# ADS1293.net
KiCad netlist of a schematic drawn in EasyEDA
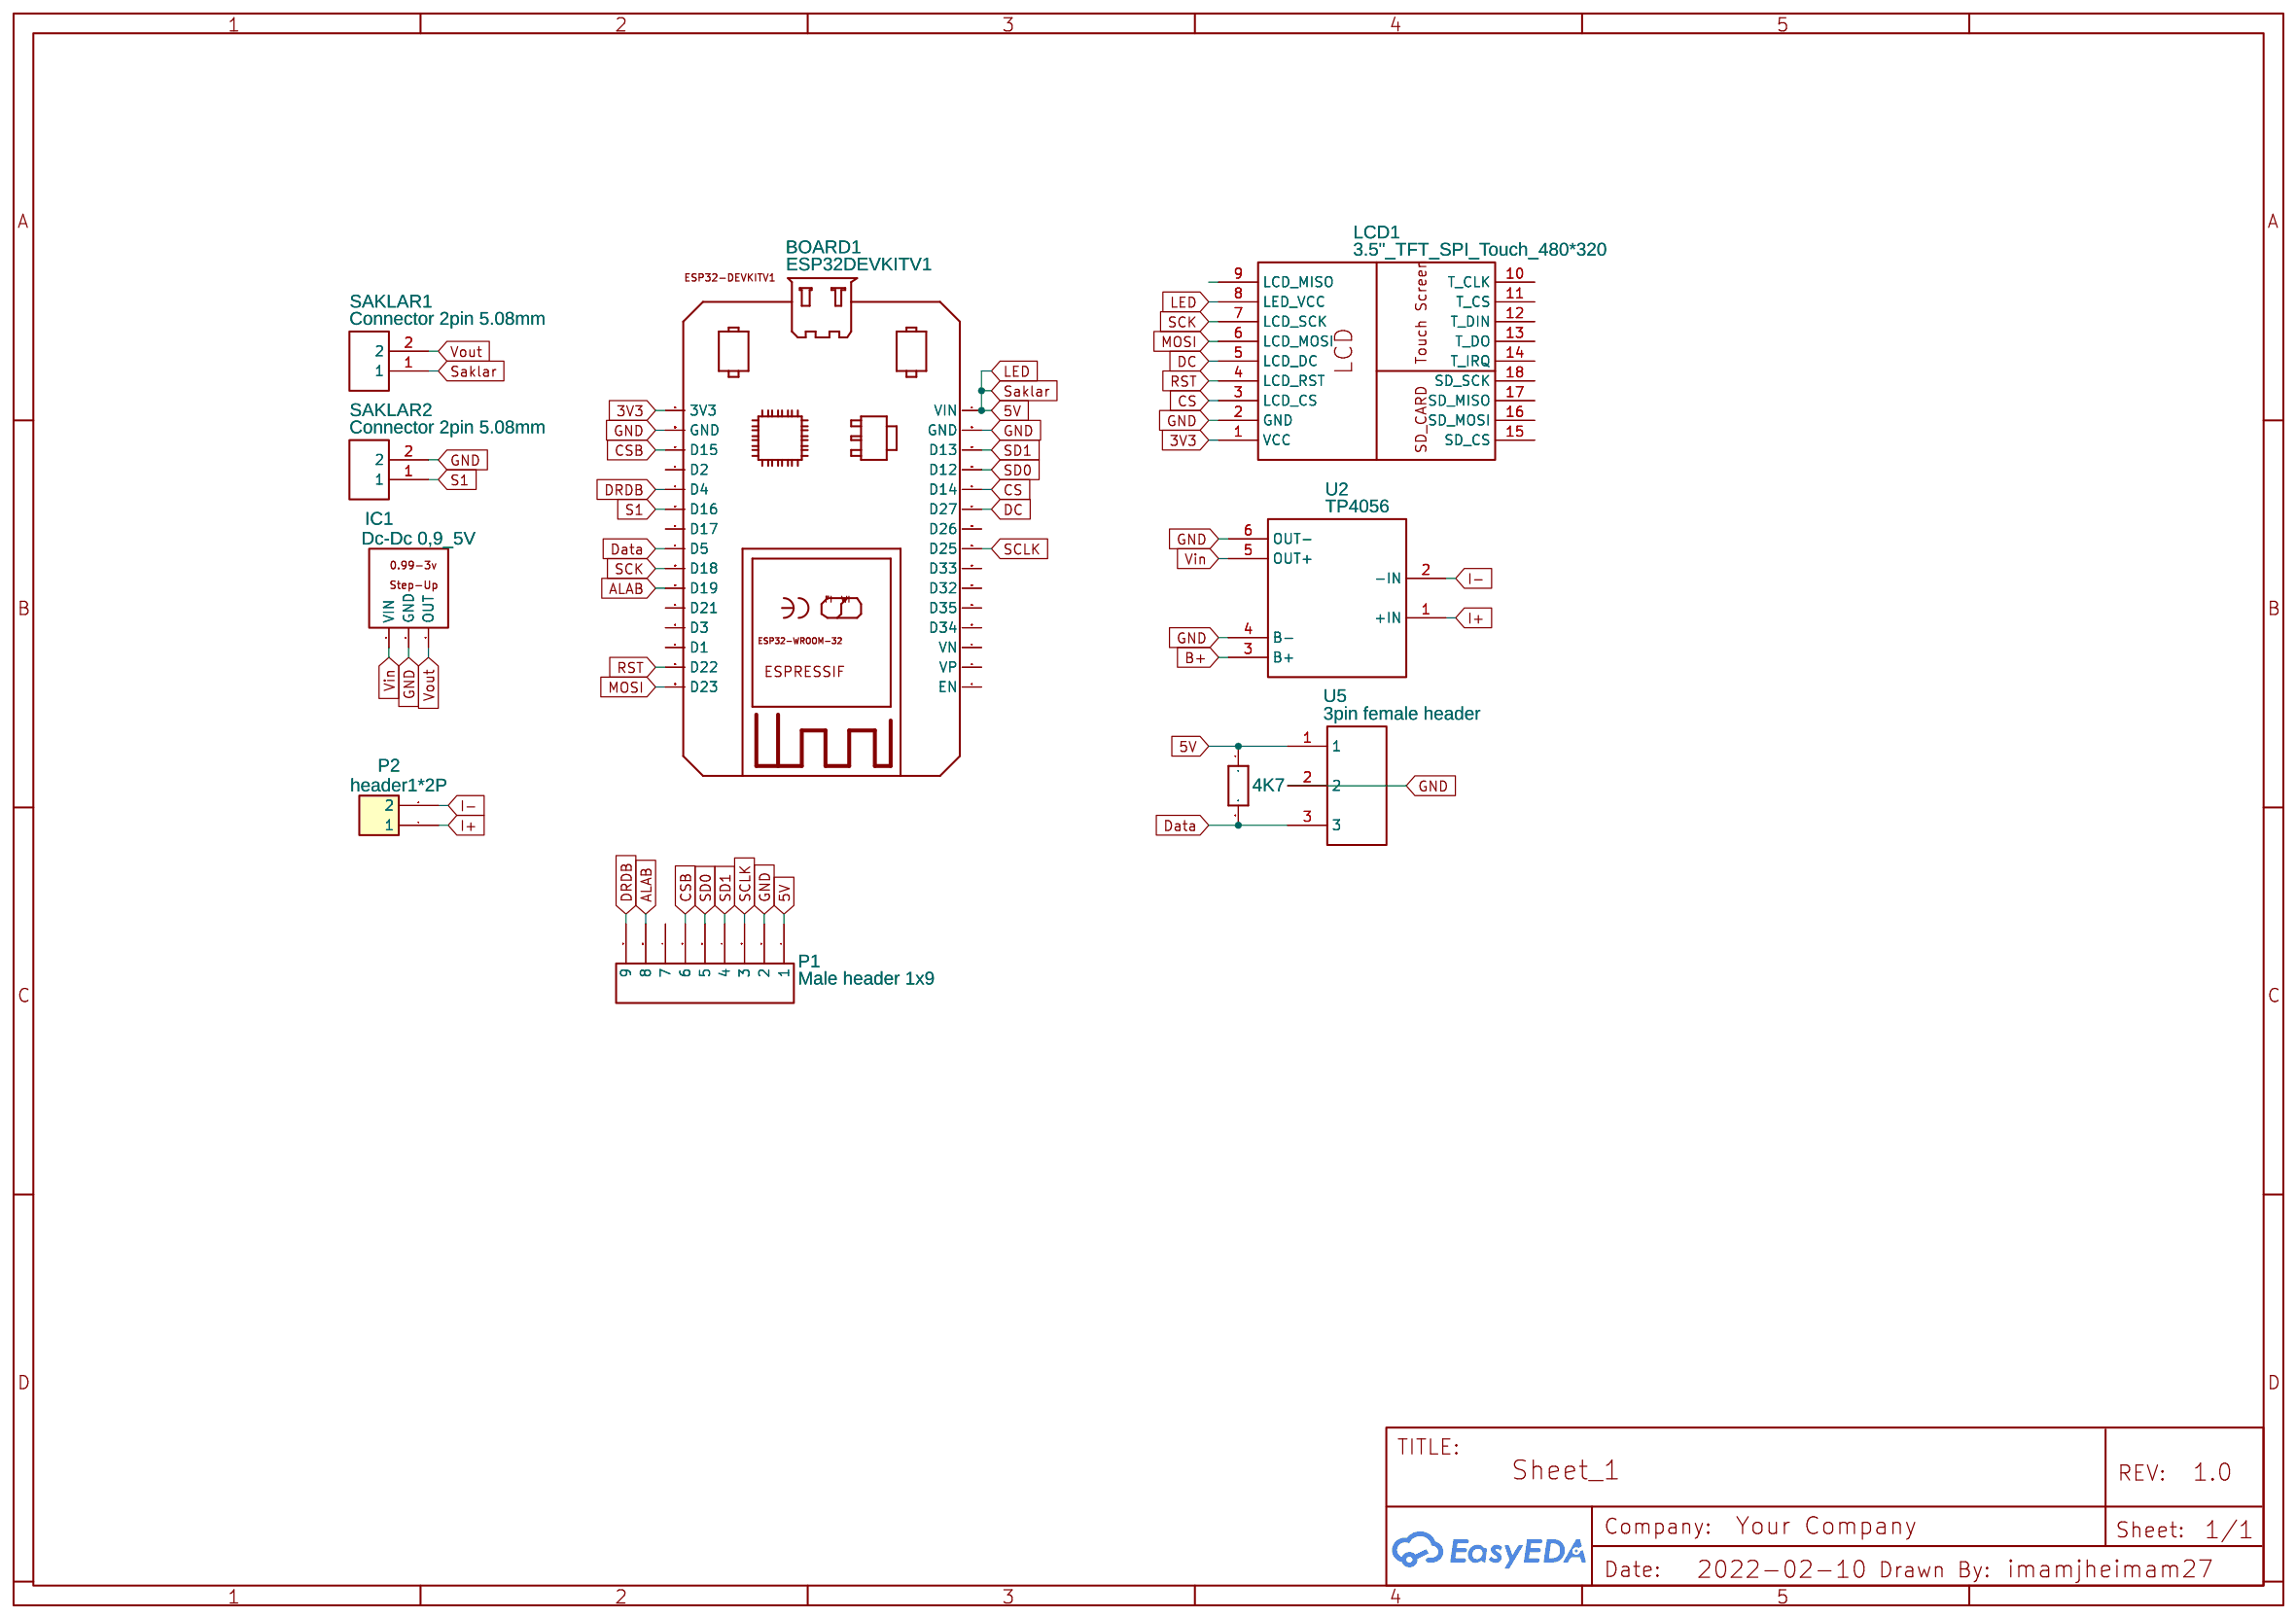
[diagram p0: schematic sheet]

(export (version "E")
  (design (tool "Eeschema 10.0.6"))
  (components
    (comp (ref "4K7") (value ".") (libsource (lib "") (part "NFR25H0002208J")))
    (comp (ref "BOARD1") (value "ESP32DEVKITV1") (libsource (lib "") (part "ESP32DEVKITV1")))
    (comp (ref "IC1") (value "Dc-Dc 0,9_5V") (libsource (lib "") (part "Dc-Dc 0,9_5V")))
    (comp (ref "LCD1")
      (value "3.5\"_TFT_SPI_Touch_480*320")
      (fields (field (name "BOM_Manufacturer Part") "ILI 9488"))
      (libsource (lib "") (part "3.5&quot;_TFT_SPI_Touch_480*320"))
    )
    (comp (ref "P1")
      (value "Male header 1x9")
      (fields
        (field (name "BOM_Manufacturer Part") "Pin Header 2.54mm Pitch 11 Pin Female Single Row Right Angle Strip")
      )
      (libsource (lib "") (part "Male header 1x9"))
    )
    (comp (ref "P2") (value "header1*2P") (libsource (lib "") (part "header1*2P")))
    (comp (ref "SAKLAR1") (value "Connector 2pin 5.08mm") (libsource (lib "") (part "Connector 2pin 5.08mm")))
    (comp (ref "SAKLAR2") (value "Connector 2pin 5.08mm") (libsource (lib "") (part "Connector 2pin 5.08mm")))
    (comp (ref "U2") (value "TP4056") (libsource (lib "") (part "TP4056")))
    (comp (ref "U5") (value "3pin female header") (libsource (lib "") (part "3pin female header")))
  )
  (nets
    (net (code "1") (name "3V3") (class "Default")
      (node (ref "BOARD1") (pin "3V3") (pinfunction "3V3_3V3") (pintype "bidirectional"))
      (node (ref "LCD1") (pin "1") (pinfunction "VCC_1") (pintype "unspecified"))
    )
    (net (code "2") (name "5V") (class "Default")
      (node (ref "4K7") (pin "1") (pinfunction "1_1") (pintype "bidirectional"))
      (node (ref "BOARD1") (pin "VIN") (pinfunction "VIN_VIN") (pintype "bidirectional"))
      (node (ref "LCD1") (pin "8") (pinfunction "LED_VCC_8") (pintype "unspecified"))
      (node (ref "P1") (pin "1") (pinfunction "1_1") (pintype "input"))
      (node (ref "SAKLAR1") (pin "1") (pinfunction "1_1") (pintype "unspecified"))
      (node (ref "U5") (pin "1") (pinfunction "1_1") (pintype "unspecified"))
    )
    (net (code "3") (name "ALAB") (class "Default")
      (node (ref "BOARD1") (pin "D19") (pinfunction "D19_D19") (pintype "bidirectional"))
      (node (ref "P1") (pin "8") (pinfunction "8_8") (pintype "input"))
    )
    (net (code "4") (name "B+") (class "Default")
      (node (ref "U2") (pin "3") (pinfunction "B+_3") (pintype "unspecified"))
    )
    (net (code "5") (name "CS") (class "Default")
      (node (ref "BOARD1") (pin "D14") (pinfunction "D14_D14") (pintype "bidirectional"))
      (node (ref "LCD1") (pin "3") (pinfunction "LCD_CS_3") (pintype "unspecified"))
    )
    (net (code "6") (name "CSB") (class "Default")
      (node (ref "BOARD1") (pin "D15") (pinfunction "D15_D15") (pintype "bidirectional"))
      (node (ref "P1") (pin "6") (pinfunction "6_6") (pintype "input"))
    )
    (net (code "7") (name "DC") (class "Default")
      (node (ref "BOARD1") (pin "D27") (pinfunction "D27_D27") (pintype "bidirectional"))
      (node (ref "LCD1") (pin "5") (pinfunction "LCD_DC_5") (pintype "unspecified"))
    )
    (net (code "8") (name "DRDB") (class "Default")
      (node (ref "BOARD1") (pin "D4") (pinfunction "D4_D4") (pintype "bidirectional"))
      (node (ref "P1") (pin "9") (pinfunction "9_9") (pintype "input"))
    )
    (net (code "9") (name "Data") (class "Default")
      (node (ref "4K7") (pin "2") (pinfunction "2_2") (pintype "bidirectional"))
      (node (ref "BOARD1") (pin "D5") (pinfunction "D5_D5") (pintype "bidirectional"))
      (node (ref "U5") (pin "3") (pinfunction "3_3") (pintype "unspecified"))
    )
    (net (code "10") (name "GND") (class "Default")
      (node (ref "BOARD1") (pin "GND") (pinfunction "GND_GND") (pintype "bidirectional"))
      (node (ref "BOARD1") (pin "GND@1") (pinfunction "GND_GND@1") (pintype "bidirectional"))
      (node (ref "IC1") (pin "2") (pinfunction "GND_2") (pintype "unspecified"))
      (node (ref "LCD1") (pin "2") (pinfunction "GND_2") (pintype "unspecified"))
      (node (ref "P1") (pin "2") (pinfunction "2_2") (pintype "input"))
      (node (ref "SAKLAR2") (pin "2") (pinfunction "2_2") (pintype "unspecified"))
      (node (ref "U2") (pin "4") (pinfunction "B-_4") (pintype "unspecified"))
      (node (ref "U2") (pin "6") (pinfunction "OUT-_6") (pintype "unspecified"))
      (node (ref "U5") (pin "2") (pinfunction "2_2") (pintype "unspecified"))
    )
    (net (code "11") (name "I+") (class "Default")
      (node (ref "P2") (pin "1") (pinfunction "1_1") (pintype "input"))
      (node (ref "U2") (pin "1") (pinfunction "+IN_1") (pintype "unspecified"))
    )
    (net (code "12") (name "I-") (class "Default")
      (node (ref "P2") (pin "2") (pinfunction "2_2") (pintype "input"))
      (node (ref "U2") (pin "2") (pinfunction "-IN_2") (pintype "unspecified"))
    )
    (net (code "13") (name "MOSI") (class "Default")
      (node (ref "BOARD1") (pin "D23") (pinfunction "D23_D23") (pintype "bidirectional"))
      (node (ref "LCD1") (pin "6") (pinfunction "LCD_MOSI_6") (pintype "unspecified"))
    )
    (net (code "14") (name "RST") (class "Default")
      (node (ref "BOARD1") (pin "D22") (pinfunction "D22_D22") (pintype "bidirectional"))
      (node (ref "LCD1") (pin "4") (pinfunction "LCD_RST_4") (pintype "unspecified"))
    )
    (net (code "15") (name "S1") (class "Default")
      (node (ref "BOARD1") (pin "D16") (pinfunction "D16_D16") (pintype "bidirectional"))
      (node (ref "SAKLAR2") (pin "1") (pinfunction "1_1") (pintype "unspecified"))
    )
    (net (code "16") (name "SCK") (class "Default")
      (node (ref "BOARD1") (pin "D18") (pinfunction "D18_D18") (pintype "bidirectional"))
      (node (ref "LCD1") (pin "7") (pinfunction "LCD_SCK_7") (pintype "unspecified"))
    )
    (net (code "17") (name "SCLK") (class "Default")
      (node (ref "BOARD1") (pin "D25") (pinfunction "D25_D25") (pintype "bidirectional"))
      (node (ref "P1") (pin "3") (pinfunction "3_3") (pintype "input"))
    )
    (net (code "18") (name "SD0") (class "Default")
      (node (ref "BOARD1") (pin "D12") (pinfunction "D12_D12") (pintype "bidirectional"))
      (node (ref "P1") (pin "5") (pinfunction "5_5") (pintype "input"))
    )
    (net (code "19") (name "SD1") (class "Default")
      (node (ref "BOARD1") (pin "D13") (pinfunction "D13_D13") (pintype "bidirectional"))
      (node (ref "P1") (pin "4") (pinfunction "4_4") (pintype "input"))
    )
    (net (code "20") (name "Vin") (class "Default")
      (node (ref "IC1") (pin "1") (pinfunction "VIN_1") (pintype "unspecified"))
      (node (ref "U2") (pin "5") (pinfunction "OUT+_5") (pintype "unspecified"))
    )
    (net (code "21") (name "Vout") (class "Default")
      (node (ref "IC1") (pin "3") (pinfunction "OUT_3") (pintype "unspecified"))
      (node (ref "SAKLAR1") (pin "2") (pinfunction "2_2") (pintype "unspecified"))
    )
    (net (code "22") (name "unconnected-(BOARD1-PadD1)") (class "Default")
      (node (ref "BOARD1") (pin "D1") (pinfunction "D1_D1") (pintype "bidirectional"))
    )
    (net (code "23") (name "unconnected-(BOARD1-PadD2)") (class "Default")
      (node (ref "BOARD1") (pin "D2") (pinfunction "D2_D2") (pintype "bidirectional"))
    )
    (net (code "24") (name "unconnected-(BOARD1-PadD3)") (class "Default")
      (node (ref "BOARD1") (pin "D3") (pinfunction "D3_D3") (pintype "bidirectional"))
    )
    (net (code "25") (name "unconnected-(BOARD1-PadD17)") (class "Default")
      (node (ref "BOARD1") (pin "D17") (pinfunction "D17_D17") (pintype "bidirectional"))
    )
    (net (code "26") (name "unconnected-(BOARD1-PadD21)") (class "Default")
      (node (ref "BOARD1") (pin "D21") (pinfunction "D21_D21") (pintype "bidirectional"))
    )
    (net (code "27") (name "unconnected-(BOARD1-PadD26)") (class "Default")
      (node (ref "BOARD1") (pin "D26") (pinfunction "D26_D26") (pintype "bidirectional"))
    )
    (net (code "28") (name "unconnected-(BOARD1-PadD32)") (class "Default")
      (node (ref "BOARD1") (pin "D32") (pinfunction "D32_D32") (pintype "bidirectional"))
    )
    (net (code "29") (name "unconnected-(BOARD1-PadD33)") (class "Default")
      (node (ref "BOARD1") (pin "D33") (pinfunction "D33_D33") (pintype "bidirectional"))
    )
    (net (code "30") (name "unconnected-(BOARD1-PadD34)") (class "Default")
      (node (ref "BOARD1") (pin "D34") (pinfunction "D34_D34") (pintype "bidirectional"))
    )
    (net (code "31") (name "unconnected-(BOARD1-PadD35)") (class "Default")
      (node (ref "BOARD1") (pin "D35") (pinfunction "D35_D35") (pintype "bidirectional"))
    )
    (net (code "32") (name "unconnected-(BOARD1-PadEN)") (class "Default")
      (node (ref "BOARD1") (pin "EN") (pinfunction "EN_EN") (pintype "bidirectional"))
    )
    (net (code "33") (name "unconnected-(BOARD1-PadVN)") (class "Default")
      (node (ref "BOARD1") (pin "VN") (pinfunction "VN_VN") (pintype "bidirectional"))
    )
    (net (code "34") (name "unconnected-(BOARD1-PadVP)") (class "Default")
      (node (ref "BOARD1") (pin "VP") (pinfunction "VP_VP") (pintype "bidirectional"))
    )
    (net (code "35") (name "unconnected-(LCD1-LCD_MISO-Pad9)") (class "Default")
      (node (ref "LCD1") (pin "9") (pinfunction "LCD_MISO_9") (pintype "unspecified"))
    )
    (net (code "36") (name "unconnected-(LCD1-SD_CS-Pad15)") (class "Default")
      (node (ref "LCD1") (pin "15") (pinfunction "SD_CS_15") (pintype "unspecified"))
    )
    (net (code "37") (name "unconnected-(LCD1-SD_MISO-Pad17)") (class "Default")
      (node (ref "LCD1") (pin "17") (pinfunction "SD_MISO_17") (pintype "unspecified"))
    )
    (net (code "38") (name "unconnected-(LCD1-SD_MOSI-Pad16)") (class "Default")
      (node (ref "LCD1") (pin "16") (pinfunction "SD_MOSI_16") (pintype "unspecified"))
    )
    (net (code "39") (name "unconnected-(LCD1-SD_SCK-Pad18)") (class "Default")
      (node (ref "LCD1") (pin "18") (pinfunction "SD_SCK_18") (pintype "unspecified"))
    )
    (net (code "40") (name "unconnected-(LCD1-T_CLK-Pad10)") (class "Default")
      (node (ref "LCD1") (pin "10") (pinfunction "T_CLK_10") (pintype "unspecified"))
    )
    (net (code "41") (name "unconnected-(LCD1-T_CS-Pad11)") (class "Default")
      (node (ref "LCD1") (pin "11") (pinfunction "T_CS_11") (pintype "unspecified"))
    )
    (net (code "42") (name "unconnected-(LCD1-T_DIN-Pad12)") (class "Default")
      (node (ref "LCD1") (pin "12") (pinfunction "T_DIN_12") (pintype "unspecified"))
    )
    (net (code "43") (name "unconnected-(LCD1-T_DO-Pad13)") (class "Default")
      (node (ref "LCD1") (pin "13") (pinfunction "T_DO_13") (pintype "unspecified"))
    )
    (net (code "44") (name "unconnected-(LCD1-T_IRQ-Pad14)") (class "Default")
      (node (ref "LCD1") (pin "14") (pinfunction "T_IRQ_14") (pintype "unspecified"))
    )
    (net (code "45") (name "unconnected-(P1-Pad7)") (class "Default")
      (node (ref "P1") (pin "7") (pinfunction "7_7") (pintype "input"))
    )
  )
)
